# hex-inverter.net
KiCad netlist of a schematic drawn in Altium Designer
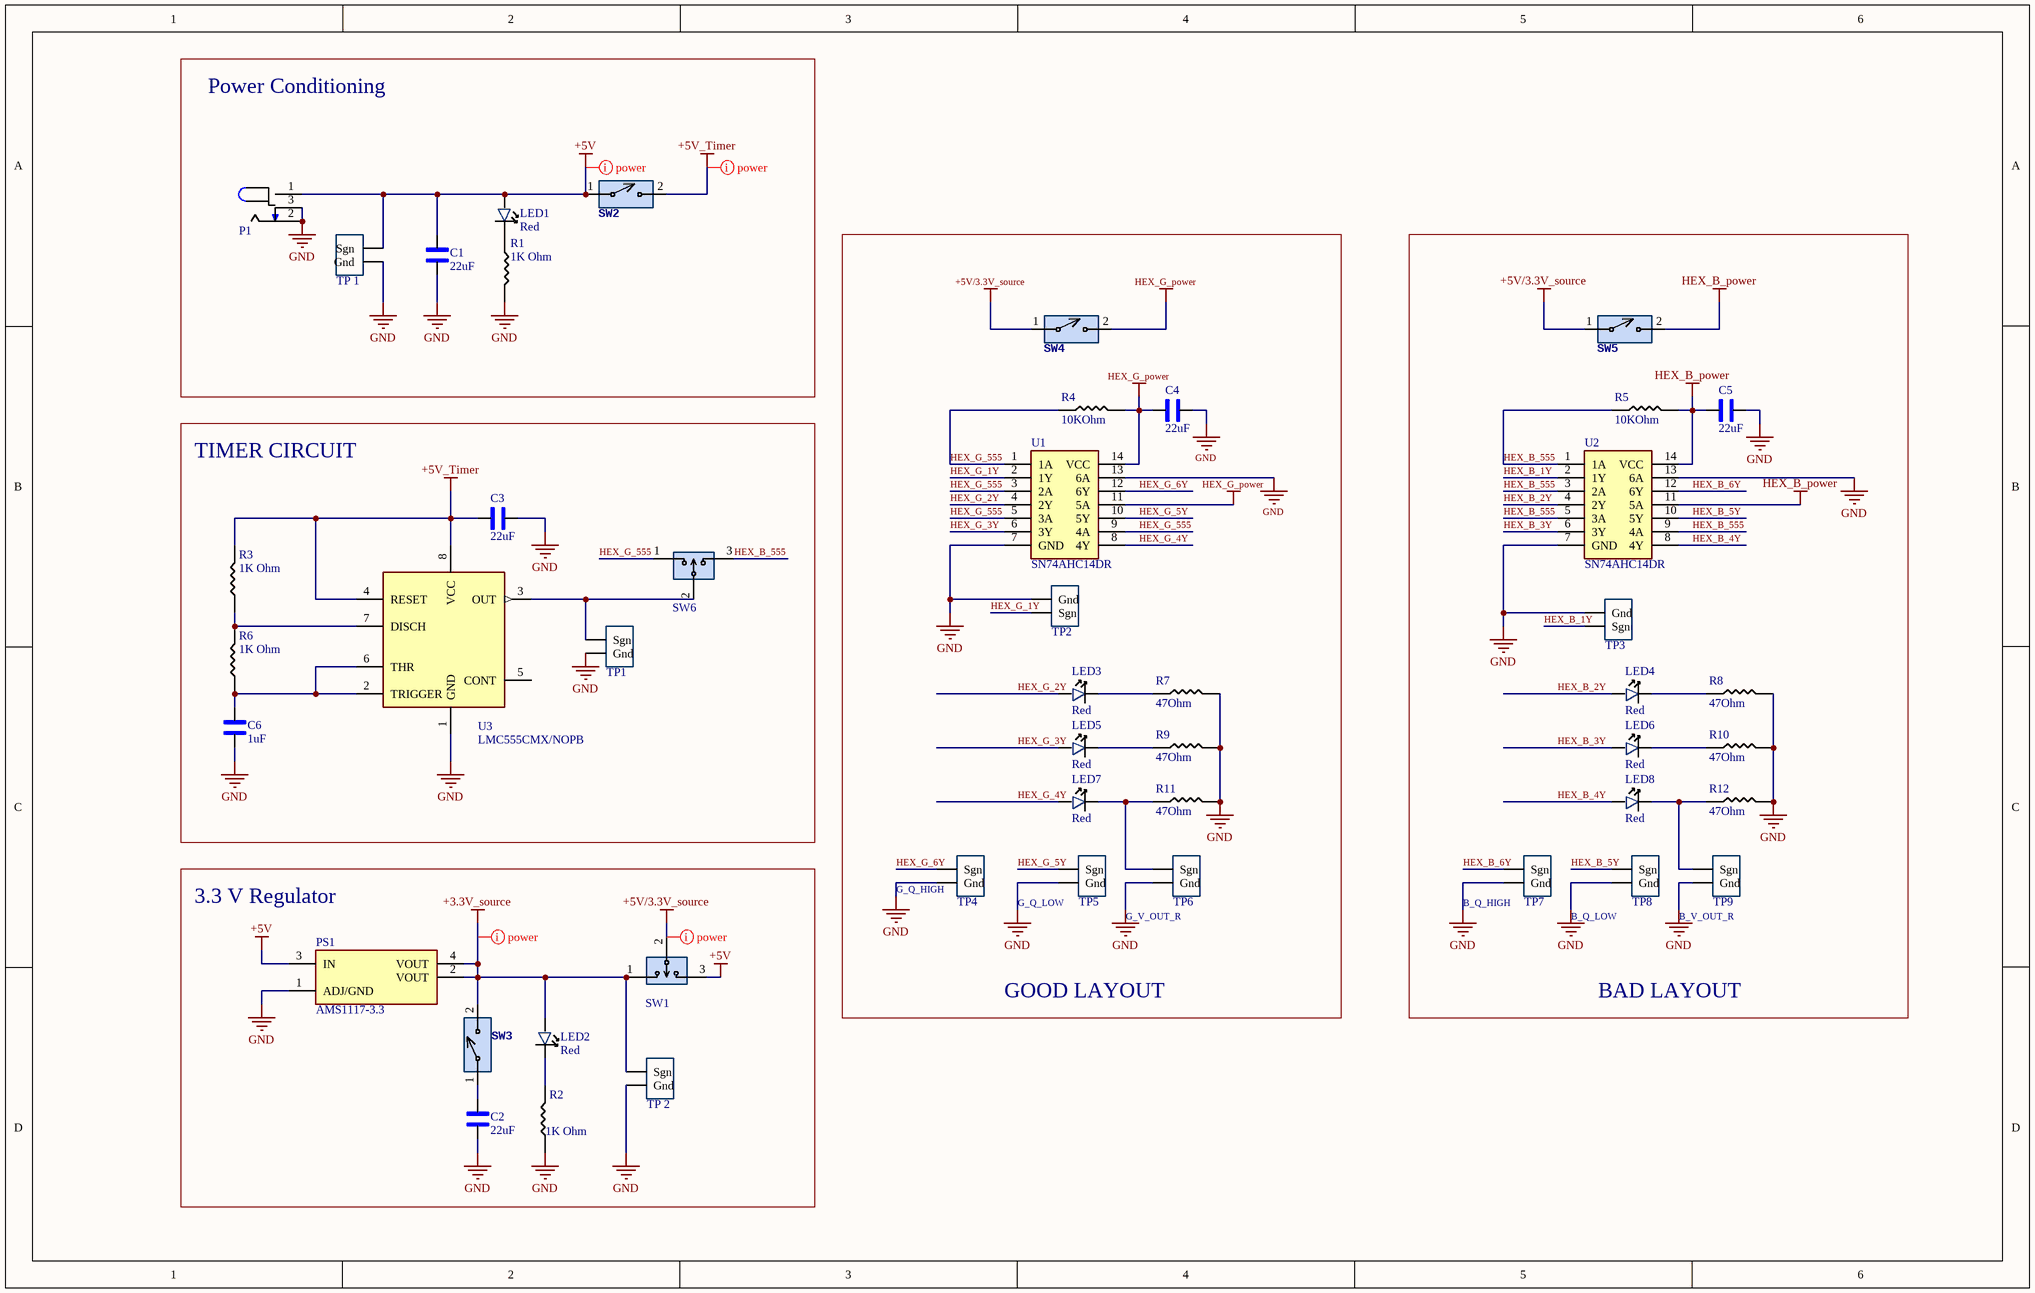
[diagram p0: hex-inverter.SchDoc]

(export (version "E")
  (design (tool "Eeschema 10.0.6"))
  (components
    (comp (ref "C1")
      (value "22uF")
      (footprint "1206_Passive_Capacitor")
      (description "22uF ±10% 25V X5R 1206 Multilayer Ceramic Capacitors MLCC - SMD/SMT RoHS")
      (fields (field (name "MFR PART #") "CL31A226KAHNNNE") (field (name "LCSC PART#") "C12891"))
      (libsource (lib "ECEN5730Lib_2023_05_DS") (part "C_22uF_1206"))
    )
    (comp (ref "C2")
      (value "22uF")
      (footprint "1206_Passive_Capacitor")
      (description "22uF ±10% 25V X5R 1206 Multilayer Ceramic Capacitors MLCC - SMD/SMT RoHS")
      (fields (field (name "MFR PART #") "CL31A226KAHNNNE") (field (name "LCSC PART#") "C12891"))
      (libsource (lib "ECEN5730Lib_2023_05_DS") (part "C_22uF_1206"))
    )
    (comp (ref "C3")
      (value "22uF")
      (footprint "1206_Passive_Capacitor")
      (description "22uF ±10% 25V X5R 1206 Multilayer Ceramic Capacitors MLCC - SMD/SMT RoHS")
      (fields (field (name "MFR PART #") "CL31A226KAHNNNE") (field (name "LCSC PART#") "C12891"))
      (libsource (lib "ECEN5730Lib_2023_05_DS") (part "C_22uF_1206"))
    )
    (comp (ref "C4")
      (value "22uF")
      (footprint "1206_Passive_Capacitor")
      (description "22uF ±10% 25V X5R 1206 Multilayer Ceramic Capacitors MLCC - SMD/SMT RoHS")
      (fields (field (name "MFR PART #") "CL31A226KAHNNNE") (field (name "LCSC PART#") "C12891"))
      (libsource (lib "ECEN5730Lib_2023_05_DS") (part "C_22uF_1206"))
    )
    (comp (ref "C5")
      (value "22uF")
      (footprint "1206_Passive_Capacitor")
      (description "22uF ±10% 25V X5R 1206 Multilayer Ceramic Capacitors MLCC - SMD/SMT RoHS")
      (fields (field (name "MFR PART #") "CL31A226KAHNNNE") (field (name "LCSC PART#") "C12891"))
      (libsource (lib "ECEN5730Lib_2023_05_DS") (part "C_22uF_1206"))
    )
    (comp (ref "C6")
      (value "1uF")
      (footprint "1206_Passive_Capacitor")
      (description "MULTILAYER CERAMIC CAPACITORS MLCC - SMD/SMT 1UF 50V 1206 ROHS")
      (fields (field (name "MFR PART #") "CL31B105KBHNNNE") (field (name "LCSC PART#") "C1848"))
      (libsource (lib "ECEN5730Lib_2023_05_DS") (part "C_1uF_1206"))
    )
    (comp (ref "LED1")
      (value "Red")
      (footprint "LED_1206")
      (description "Red 621~631nm 1206 Light Emitting Diodes (LED) RoHS")
      (fields (field (name "MFR PART #") "15-21/R6C-FQ1R1B/2T") (field (name "LCSC PART#") "C93133"))
      (libsource (lib "ECEN5730Lib_2023_05_DS") (part "LED_RED_1206"))
    )
    (comp (ref "LED2")
      (value "Red")
      (footprint "LED_1206")
      (description "Red 621~631nm 1206 Light Emitting Diodes (LED) RoHS")
      (fields (field (name "MFR PART #") "15-21/R6C-FQ1R1B/2T") (field (name "LCSC PART#") "C93133"))
      (libsource (lib "ECEN5730Lib_2023_05_DS") (part "LED_RED_1206"))
    )
    (comp (ref "LED3")
      (value "Red")
      (footprint "LED_1206")
      (description "Red 621~631nm 1206 Light Emitting Diodes (LED) RoHS")
      (fields (field (name "MFR PART #") "15-21/R6C-FQ1R1B/2T") (field (name "LCSC PART#") "C93133"))
      (libsource (lib "ECEN5730Lib_2023_05_DS") (part "LED_RED_1206"))
    )
    (comp (ref "LED4")
      (value "Red")
      (footprint "LED_1206")
      (description "Red 621~631nm 1206 Light Emitting Diodes (LED) RoHS")
      (fields (field (name "MFR PART #") "15-21/R6C-FQ1R1B/2T") (field (name "LCSC PART#") "C93133"))
      (libsource (lib "ECEN5730Lib_2023_05_DS") (part "LED_RED_1206"))
    )
    (comp (ref "LED5")
      (value "Red")
      (footprint "LED_1206")
      (description "Red 621~631nm 1206 Light Emitting Diodes (LED) RoHS")
      (fields (field (name "MFR PART #") "15-21/R6C-FQ1R1B/2T") (field (name "LCSC PART#") "C93133"))
      (libsource (lib "ECEN5730Lib_2023_05_DS") (part "LED_RED_1206"))
    )
    (comp (ref "LED6")
      (value "Red")
      (footprint "LED_1206")
      (description "Red 621~631nm 1206 Light Emitting Diodes (LED) RoHS")
      (fields (field (name "MFR PART #") "15-21/R6C-FQ1R1B/2T") (field (name "LCSC PART#") "C93133"))
      (libsource (lib "ECEN5730Lib_2023_05_DS") (part "LED_RED_1206"))
    )
    (comp (ref "LED7")
      (value "Red")
      (footprint "LED_1206")
      (description "Red 621~631nm 1206 Light Emitting Diodes (LED) RoHS")
      (fields (field (name "MFR PART #") "15-21/R6C-FQ1R1B/2T") (field (name "LCSC PART#") "C93133"))
      (libsource (lib "ECEN5730Lib_2023_05_DS") (part "LED_RED_1206"))
    )
    (comp (ref "LED8")
      (value "Red")
      (footprint "LED_1206")
      (description "Red 621~631nm 1206 Light Emitting Diodes (LED) RoHS")
      (fields (field (name "MFR PART #") "15-21/R6C-FQ1R1B/2T") (field (name "LCSC PART#") "C93133"))
      (libsource (lib "ECEN5730Lib_2023_05_DS") (part "LED_RED_1206"))
    )
    (comp (ref "P1")
      (value "Power Jack")
      (footprint "Power_Jack")
      (description "Power Barrel Connector Jack 2.10mm ID (0.083\"), 5.50mm OD (0.217\") Through Hole, Right Angle")
      (fields (field (name "MFR PART #") "PJ-102A") (field (name "LCSC PART#") "C136744"))
      (libsource (lib "ECEN5730Lib_2023_05_DS") (part "P_Power Jack"))
    )
    (comp (ref "PS1")
      (value "AMS1117-3.3")
      (footprint "LDO")
      (description "LOW DROPOUT REGULATORS(LDO) POSITIVE FIXED 1.3V @ 800MA 15V 3.3V 1A SOT-223 ROHS")
      (fields (field (name "LCSC PART#") "C6186"))
      (libsource (lib "ECEN5730Lib_2023_05_DS") (part "PS_AMS_LDO_3v3"))
    )
    (comp (ref "R1")
      (value "1K Ohm")
      (footprint "1206_Passive_Resitor")
      (description "CHIP RESISTOR - SURFACE MOUNT 1KOHMS ±1% 1/4W 1206 ROHS")
      (fields (field (name "MFR PART #") "RNCP1206FTD1K00CT") (field (name "LCSC PART#") "C4410"))
      (libsource (lib "ECEN5730Lib_2023_05_DS") (part "R_1K_1206"))
    )
    (comp (ref "R2")
      (value "1K Ohm")
      (footprint "1206_Passive_Resitor")
      (description "CHIP RESISTOR - SURFACE MOUNT 1KOHMS ±1% 1/4W 1206 ROHS")
      (fields (field (name "MFR PART #") "RNCP1206FTD1K00CT") (field (name "LCSC PART#") "C4410"))
      (libsource (lib "ECEN5730Lib_2023_05_DS") (part "R_1K_1206"))
    )
    (comp (ref "R3")
      (value "1K Ohm")
      (footprint "1206_Passive_Resitor")
      (description "CHIP RESISTOR - SURFACE MOUNT 1KOHMS ±1% 1/4W 1206 ROHS")
      (fields (field (name "MFR PART #") "RNCP1206FTD1K00CT") (field (name "LCSC PART#") "C4410"))
      (libsource (lib "ECEN5730Lib_2023_05_DS") (part "R_1K_1206"))
    )
    (comp (ref "R4")
      (value "10KOhm")
      (footprint "1206_Passive_Resitor")
      (description "10 kOhms ±5% 0.25W, 1/4W Chip Resistor 1206 (3216 Metric) Automotive AEC-Q200 Thick Film")
      (fields (field (name "MFR PART #") "RMCF1206FT10K0") (field (name "LCSC PART#") "C17902"))
      (libsource (lib "ECEN5730Lib_2023_05_DS") (part "R_10KOhm_1206"))
    )
    (comp (ref "R5")
      (value "10KOhm")
      (footprint "1206_Passive_Resitor")
      (description "10 kOhms ±5% 0.25W, 1/4W Chip Resistor 1206 (3216 Metric) Automotive AEC-Q200 Thick Film")
      (fields (field (name "MFR PART #") "RMCF1206FT10K0") (field (name "LCSC PART#") "C17902"))
      (libsource (lib "ECEN5730Lib_2023_05_DS") (part "R_10KOhm_1206"))
    )
    (comp (ref "R6")
      (value "1K Ohm")
      (footprint "1206_Passive_Resitor")
      (description "CHIP RESISTOR - SURFACE MOUNT 1KOHMS ±1% 1/4W 1206 ROHS")
      (fields (field (name "MFR PART #") "RNCP1206FTD1K00CT") (field (name "LCSC PART#") "C4410"))
      (libsource (lib "ECEN5730Lib_2023_05_DS") (part "R_1K_1206"))
    )
    (comp (ref "R7")
      (value "47Ohm")
      (footprint "1206_Passive_Resitor")
      (description "47Ω ±5% 0.25W ±200ppm/℃ 1206 Chip Resistor - Surface Mount RoHS")
      (fields (field (name "MFR PART #") "1206W4J0470T5E") (field (name "LCSC PART#") "C25384"))
      (libsource (lib "ECEN5730Lib_2023_05_DS") (part "R_47Ohm_1206"))
    )
    (comp (ref "R8")
      (value "47Ohm")
      (footprint "1206_Passive_Resitor")
      (description "47Ω ±5% 0.25W ±200ppm/℃ 1206 Chip Resistor - Surface Mount RoHS")
      (fields (field (name "MFR PART #") "1206W4J0470T5E") (field (name "LCSC PART#") "C25384"))
      (libsource (lib "ECEN5730Lib_2023_05_DS") (part "R_47Ohm_1206"))
    )
    (comp (ref "R9")
      (value "47Ohm")
      (footprint "1206_Passive_Resitor")
      (description "47Ω ±5% 0.25W ±200ppm/℃ 1206 Chip Resistor - Surface Mount RoHS")
      (fields (field (name "MFR PART #") "1206W4J0470T5E") (field (name "LCSC PART#") "C25384"))
      (libsource (lib "ECEN5730Lib_2023_05_DS") (part "R_47Ohm_1206"))
    )
    (comp (ref "R10")
      (value "47Ohm")
      (footprint "1206_Passive_Resitor")
      (description "47Ω ±5% 0.25W ±200ppm/℃ 1206 Chip Resistor - Surface Mount RoHS")
      (fields (field (name "MFR PART #") "1206W4J0470T5E") (field (name "LCSC PART#") "C25384"))
      (libsource (lib "ECEN5730Lib_2023_05_DS") (part "R_47Ohm_1206"))
    )
    (comp (ref "R11")
      (value "47Ohm")
      (footprint "1206_Passive_Resitor")
      (description "47Ω ±5% 0.25W ±200ppm/℃ 1206 Chip Resistor - Surface Mount RoHS")
      (fields (field (name "MFR PART #") "1206W4J0470T5E") (field (name "LCSC PART#") "C25384"))
      (libsource (lib "ECEN5730Lib_2023_05_DS") (part "R_47Ohm_1206"))
    )
    (comp (ref "R12")
      (value "47Ohm")
      (footprint "1206_Passive_Resitor")
      (description "47Ω ±5% 0.25W ±200ppm/℃ 1206 Chip Resistor - Surface Mount RoHS")
      (fields (field (name "MFR PART #") "1206W4J0470T5E") (field (name "LCSC PART#") "C25384"))
      (libsource (lib "ECEN5730Lib_2023_05_DS") (part "R_47Ohm_1206"))
    )
    (comp (ref "SW1")
      (value "PREC003SAAN-RC")
      (footprint "3_PIN_100mil")
      (description "Connector Header Through Hole 3 position 0.100\" (2.54mm)")
      (fields (field (name "LCSC PART#") "C49257"))
      (libsource (lib "ECEN5730Lib_2023_05_DS") (part "SW_3Pin_100mil_Switch"))
    )
    (comp (ref "SW2")
      (value "SW_2Pin_100mil_Switch")
      (footprint "2Pin-Header-Conn")
      (description "2Pin Header")
      (fields (field (name "LCSC PART#") "C124375"))
      (libsource (lib "ECEN5730Lib_2023_05_DS") (part "SW_2Pin_100mil_Switch"))
    )
    (comp (ref "SW3")
      (value "SW_2Pin_100mil_Switch")
      (footprint "2Pin-Header-Conn")
      (description "2Pin Header")
      (fields (field (name "LCSC PART#") "C124375"))
      (libsource (lib "") (part "SW_2Pin_100mil_Switch_1"))
    )
    (comp (ref "SW4")
      (value "SW_2Pin_100mil_Switch")
      (footprint "2Pin-Header-Conn")
      (description "2Pin Header")
      (fields (field (name "LCSC PART#") "C124375"))
      (libsource (lib "ECEN5730Lib_2023_05_DS") (part "SW_2Pin_100mil_Switch"))
    )
    (comp (ref "SW5")
      (value "SW_2Pin_100mil_Switch")
      (footprint "2Pin-Header-Conn")
      (description "2Pin Header")
      (fields (field (name "LCSC PART#") "C124375"))
      (libsource (lib "ECEN5730Lib_2023_05_DS") (part "SW_2Pin_100mil_Switch"))
    )
    (comp (ref "SW6")
      (value "PREC003SAAN-RC")
      (footprint "3_PIN_100mil")
      (description "Connector Header Through Hole 3 position 0.100\" (2.54mm)")
      (fields (field (name "LCSC PART#") "C49257"))
      (libsource (lib "") (part "SW_3Pin_100mil_Switch_1"))
    )
    (comp (ref "TP 1")
      (value "10x Probe TP")
      (footprint "TP10x_Probe")
      (description "Test Point 300 mil centers")
      (libsource (lib "") (part "TP_10x_Probe_2"))
    )
    (comp (ref "TP 2")
      (value "10x Probe TP")
      (footprint "TP10x_Probe")
      (description "Test Point 300 mil centers")
      (libsource (lib "ECEN5730Lib_2023_05_DS") (part "TP_10x_Probe"))
    )
    (comp (ref "TP1")
      (value "10x Probe TP")
      (footprint "TP10x_Probe")
      (description "Test Point 300 mil centers")
      (libsource (lib "ECEN5730Lib_2023_05_DS") (part "TP_10x_Probe"))
    )
    (comp (ref "TP2")
      (value "10x Probe TP")
      (footprint "TP10x_Probe")
      (description "Test Point 300 mil centers")
      (libsource (lib "") (part "TP_10x_Probe_1"))
    )
    (comp (ref "TP3")
      (value "10x Probe TP")
      (footprint "TP10x_Probe")
      (description "Test Point 300 mil centers")
      (libsource (lib "") (part "TP_10x_Probe_1"))
    )
    (comp (ref "TP4")
      (value "10x Probe TP")
      (footprint "TP10x_Probe")
      (description "Test Point 300 mil centers")
      (libsource (lib "ECEN5730Lib_2023_05_DS") (part "TP_10x_Probe"))
    )
    (comp (ref "TP5")
      (value "10x Probe TP")
      (footprint "TP10x_Probe")
      (description "Test Point 300 mil centers")
      (libsource (lib "ECEN5730Lib_2023_05_DS") (part "TP_10x_Probe"))
    )
    (comp (ref "TP6")
      (value "10x Probe TP")
      (footprint "TP10x_Probe")
      (description "Test Point 300 mil centers")
      (libsource (lib "ECEN5730Lib_2023_05_DS") (part "TP_10x_Probe"))
    )
    (comp (ref "TP7")
      (value "10x Probe TP")
      (footprint "TP10x_Probe")
      (description "Test Point 300 mil centers")
      (libsource (lib "ECEN5730Lib_2023_05_DS") (part "TP_10x_Probe"))
    )
    (comp (ref "TP8")
      (value "10x Probe TP")
      (footprint "TP10x_Probe")
      (description "Test Point 300 mil centers")
      (libsource (lib "ECEN5730Lib_2023_05_DS") (part "TP_10x_Probe"))
    )
    (comp (ref "TP9")
      (value "10x Probe TP")
      (footprint "TP10x_Probe")
      (description "Test Point 300 mil centers")
      (libsource (lib "ECEN5730Lib_2023_05_DS") (part "TP_10x_Probe"))
    )
    (comp (ref "U1")
      (value "SN74AHC14DR")
      (footprint "HEX_74AC14")
      (description "Inverter IC 6 Channel Schmitt Trigger 14-SOIC")
      (fields (field (name "LCSC PART#") "C6942"))
      (libsource (lib "ECEN5730Lib_2023_05_DS") (part "U_74AHC14"))
    )
    (comp (ref "U2")
      (value "SN74AHC14DR")
      (footprint "HEX_74AC14")
      (description "Inverter IC 6 Channel Schmitt Trigger 14-SOIC")
      (fields (field (name "LCSC PART#") "C6942"))
      (libsource (lib "ECEN5730Lib_2023_05_DS") (part "U_74AHC14"))
    )
    (comp (ref "U3")
      (value "LMC555CMX/NOPB")
      (footprint "TS555IDTTR")
      (description "555 Type, Timer/Oscillator _Single_ IC 3MHz 8-SO")
      (fields (field (name "LCSC PART#") "C90760"))
      (libsource (lib "ECEN5730Lib_2023_05_DS") (part "U_555_Fast"))
    )
  )
  (nets
    (net (code "1") (name "+3.3V_source") (class "Default")
      (node (ref "LED2") (pin "1") (pinfunction "1_1") (pintype "passive"))
      (node (ref "PS1") (pin "2") (pinfunction "VOUT_2") (pintype "power_in"))
      (node (ref "PS1") (pin "4") (pinfunction "VOUT_4") (pintype "power_in"))
      (node (ref "SW1") (pin "1") (pinfunction "1_1") (pintype "passive"))
      (node (ref "SW3") (pin "2") (pinfunction "2_2") (pintype "passive"))
      (node (ref "TP 2") (pin "1") (pinfunction "Sgn_1") (pintype "passive"))
    )
    (net (code "2") (name "+5V") (class "Default")
      (node (ref "C1") (pin "2") (pinfunction "2_2") (pintype "passive"))
      (node (ref "LED1") (pin "1") (pinfunction "1_1") (pintype "passive"))
      (node (ref "P1") (pin "1") (pinfunction "1_1") (pintype "power_in"))
      (node (ref "PS1") (pin "3") (pinfunction "IN_3") (pintype "power_in"))
      (node (ref "SW1") (pin "3") (pinfunction "3_3") (pintype "passive"))
      (node (ref "SW2") (pin "1") (pinfunction "1_1") (pintype "passive"))
      (node (ref "TP 1") (pin "1") (pinfunction "Sgn_1") (pintype "passive"))
    )
    (net (code "3") (name "+5V_Timer") (class "Default")
      (node (ref "C3") (pin "2") (pinfunction "2_2") (pintype "passive"))
      (node (ref "R3") (pin "2") (pinfunction "2_2") (pintype "passive"))
      (node (ref "SW2") (pin "2") (pinfunction "2_2") (pintype "passive"))
      (node (ref "U3") (pin "4") (pinfunction "RESET_4") (pintype "passive"))
      (node (ref "U3") (pin "8") (pinfunction "VCC_8") (pintype "power_in"))
    )
    (net (code "4") (name "+5V{slash}3.3V_source") (class "Default")
      (node (ref "SW1") (pin "2") (pinfunction "2_2") (pintype "passive"))
      (node (ref "SW4") (pin "1") (pinfunction "1_1") (pintype "passive"))
      (node (ref "SW5") (pin "1") (pinfunction "1_1") (pintype "passive"))
    )
    (net (code "5") (name "/HEX_B_1Y") (class "Default")
      (node (ref "TP3") (pin "1") (pinfunction "Sgn_1") (pintype "passive"))
      (node (ref "U2") (pin "2") (pinfunction "1Y_2") (pintype "passive"))
    )
    (net (code "6") (name "/HEX_B_2Y") (class "Default")
      (node (ref "LED4") (pin "1") (pinfunction "1_1") (pintype "passive"))
      (node (ref "U2") (pin "4") (pinfunction "2Y_4") (pintype "passive"))
    )
    (net (code "7") (name "/HEX_B_3Y") (class "Default")
      (node (ref "LED6") (pin "1") (pinfunction "1_1") (pintype "passive"))
      (node (ref "U2") (pin "6") (pinfunction "3Y_6") (pintype "passive"))
    )
    (net (code "8") (name "/HEX_B_4Y") (class "Default")
      (node (ref "LED8") (pin "1") (pinfunction "1_1") (pintype "passive"))
      (node (ref "U2") (pin "8") (pinfunction "4Y_8") (pintype "passive"))
    )
    (net (code "9") (name "/HEX_B_5Y") (class "Default")
      (node (ref "TP8") (pin "1") (pinfunction "Sgn_1") (pintype "passive"))
      (node (ref "U2") (pin "10") (pinfunction "5Y_10") (pintype "passive"))
    )
    (net (code "10") (name "/HEX_B_6Y") (class "Default")
      (node (ref "TP7") (pin "1") (pinfunction "Sgn_1") (pintype "passive"))
      (node (ref "U2") (pin "12") (pinfunction "6Y_12") (pintype "passive"))
    )
    (net (code "11") (name "/HEX_B_555") (class "Default")
      (node (ref "R5") (pin "1") (pinfunction "1_1") (pintype "passive"))
      (node (ref "SW6") (pin "3") (pinfunction "3_3") (pintype "passive"))
      (node (ref "U2") (pin "1") (pinfunction "1A_1") (pintype "passive"))
      (node (ref "U2") (pin "3") (pinfunction "2A_3") (pintype "passive"))
      (node (ref "U2") (pin "5") (pinfunction "3A_5") (pintype "passive"))
      (node (ref "U2") (pin "9") (pinfunction "4A_9") (pintype "passive"))
    )
    (net (code "12") (name "/HEX_G_1Y") (class "Default")
      (node (ref "TP2") (pin "1") (pinfunction "Sgn_1") (pintype "passive"))
      (node (ref "U1") (pin "2") (pinfunction "1Y_2") (pintype "passive"))
    )
    (net (code "13") (name "/HEX_G_2Y") (class "Default")
      (node (ref "LED3") (pin "1") (pinfunction "1_1") (pintype "passive"))
      (node (ref "U1") (pin "4") (pinfunction "2Y_4") (pintype "passive"))
    )
    (net (code "14") (name "/HEX_G_3Y") (class "Default")
      (node (ref "LED5") (pin "1") (pinfunction "1_1") (pintype "passive"))
      (node (ref "U1") (pin "6") (pinfunction "3Y_6") (pintype "passive"))
    )
    (net (code "15") (name "/HEX_G_4Y") (class "Default")
      (node (ref "LED7") (pin "1") (pinfunction "1_1") (pintype "passive"))
      (node (ref "U1") (pin "8") (pinfunction "4Y_8") (pintype "passive"))
    )
    (net (code "16") (name "/HEX_G_5Y") (class "Default")
      (node (ref "TP5") (pin "1") (pinfunction "Sgn_1") (pintype "passive"))
      (node (ref "U1") (pin "10") (pinfunction "5Y_10") (pintype "passive"))
    )
    (net (code "17") (name "/HEX_G_6Y") (class "Default")
      (node (ref "TP4") (pin "1") (pinfunction "Sgn_1") (pintype "passive"))
      (node (ref "U1") (pin "12") (pinfunction "6Y_12") (pintype "passive"))
    )
    (net (code "18") (name "/HEX_G_555") (class "Default")
      (node (ref "R4") (pin "1") (pinfunction "1_1") (pintype "passive"))
      (node (ref "SW6") (pin "1") (pinfunction "1_1") (pintype "passive"))
      (node (ref "U1") (pin "1") (pinfunction "1A_1") (pintype "passive"))
      (node (ref "U1") (pin "3") (pinfunction "2A_3") (pintype "passive"))
      (node (ref "U1") (pin "5") (pinfunction "3A_5") (pintype "passive"))
      (node (ref "U1") (pin "9") (pinfunction "4A_9") (pintype "passive"))
    )
    (net (code "19") (name "GND") (class "Default")
      (node (ref "C1") (pin "1") (pinfunction "1_1") (pintype "passive"))
      (node (ref "C2") (pin "1") (pinfunction "1_1") (pintype "passive"))
      (node (ref "C3") (pin "1") (pinfunction "1_1") (pintype "passive"))
      (node (ref "C4") (pin "1") (pinfunction "1_1") (pintype "passive"))
      (node (ref "C5") (pin "1") (pinfunction "1_1") (pintype "passive"))
      (node (ref "C6") (pin "1") (pinfunction "1_1") (pintype "passive"))
      (node (ref "P1") (pin "2") (pinfunction "2_2") (pintype "power_in"))
      (node (ref "P1") (pin "3") (pinfunction "3_3") (pintype "power_in"))
      (node (ref "PS1") (pin "1") (pinfunction "ADJ/GND_1") (pintype "passive"))
      (node (ref "R1") (pin "2") (pinfunction "2_2") (pintype "passive"))
      (node (ref "R10") (pin "2") (pinfunction "2_2") (pintype "passive"))
      (node (ref "R11") (pin "2") (pinfunction "2_2") (pintype "passive"))
      (node (ref "R12") (pin "2") (pinfunction "2_2") (pintype "passive"))
      (node (ref "R2") (pin "1") (pinfunction "1_1") (pintype "passive"))
      (node (ref "R7") (pin "2") (pinfunction "2_2") (pintype "passive"))
      (node (ref "R8") (pin "2") (pinfunction "2_2") (pintype "passive"))
      (node (ref "R9") (pin "2") (pinfunction "2_2") (pintype "passive"))
      (node (ref "TP 1") (pin "2") (pinfunction "Gnd_2") (pintype "passive"))
      (node (ref "TP 2") (pin "2") (pinfunction "Gnd_2") (pintype "passive"))
      (node (ref "TP1") (pin "2") (pinfunction "Gnd_2") (pintype "passive"))
      (node (ref "TP2") (pin "2") (pinfunction "Gnd_2") (pintype "passive"))
      (node (ref "TP3") (pin "2") (pinfunction "Gnd_2") (pintype "passive"))
      (node (ref "TP4") (pin "2") (pinfunction "Gnd_2") (pintype "passive"))
      (node (ref "TP5") (pin "2") (pinfunction "Gnd_2") (pintype "passive"))
      (node (ref "TP6") (pin "2") (pinfunction "Gnd_2") (pintype "passive"))
      (node (ref "TP7") (pin "2") (pinfunction "Gnd_2") (pintype "passive"))
      (node (ref "TP8") (pin "2") (pinfunction "Gnd_2") (pintype "passive"))
      (node (ref "TP9") (pin "2") (pinfunction "Gnd_2") (pintype "passive"))
      (node (ref "U1") (pin "13") (pinfunction "6A_13") (pintype "passive"))
      (node (ref "U1") (pin "7") (pinfunction "GND_7") (pintype "passive"))
      (node (ref "U2") (pin "13") (pinfunction "6A_13") (pintype "passive"))
      (node (ref "U2") (pin "7") (pinfunction "GND_7") (pintype "passive"))
      (node (ref "U3") (pin "1") (pinfunction "GND_1") (pintype "power_in"))
    )
    (net (code "20") (name "HEX_B_power") (class "Default")
      (node (ref "C5") (pin "2") (pinfunction "2_2") (pintype "passive"))
      (node (ref "R5") (pin "2") (pinfunction "2_2") (pintype "passive"))
      (node (ref "SW5") (pin "2") (pinfunction "2_2") (pintype "passive"))
      (node (ref "U2") (pin "11") (pinfunction "5A_11") (pintype "passive"))
      (node (ref "U2") (pin "14") (pinfunction "VCC_14") (pintype "passive"))
    )
    (net (code "21") (name "HEX_G_power") (class "Default")
      (node (ref "C4") (pin "2") (pinfunction "2_2") (pintype "passive"))
      (node (ref "R4") (pin "2") (pinfunction "2_2") (pintype "passive"))
      (node (ref "SW4") (pin "2") (pinfunction "2_2") (pintype "passive"))
      (node (ref "U1") (pin "11") (pinfunction "5A_11") (pintype "passive"))
      (node (ref "U1") (pin "14") (pinfunction "VCC_14") (pintype "passive"))
    )
    (net (code "22") (name "Net-(C2-Pad2)") (class "Default")
      (node (ref "C2") (pin "2") (pinfunction "2_2") (pintype "passive"))
      (node (ref "SW3") (pin "1") (pinfunction "1_1") (pintype "passive"))
    )
    (net (code "23") (name "Net-(LED1-Pad2)") (class "Default")
      (node (ref "LED1") (pin "2") (pinfunction "2_2") (pintype "passive"))
      (node (ref "R1") (pin "1") (pinfunction "1_1") (pintype "passive"))
    )
    (net (code "24") (name "Net-(LED2-Pad2)") (class "Default")
      (node (ref "LED2") (pin "2") (pinfunction "2_2") (pintype "passive"))
      (node (ref "R2") (pin "2") (pinfunction "2_2") (pintype "passive"))
    )
    (net (code "25") (name "Net-(LED3-Pad2)") (class "Default")
      (node (ref "LED3") (pin "2") (pinfunction "2_2") (pintype "passive"))
      (node (ref "R7") (pin "1") (pinfunction "1_1") (pintype "passive"))
    )
    (net (code "26") (name "Net-(LED4-Pad2)") (class "Default")
      (node (ref "LED4") (pin "2") (pinfunction "2_2") (pintype "passive"))
      (node (ref "R8") (pin "1") (pinfunction "1_1") (pintype "passive"))
    )
    (net (code "27") (name "Net-(LED5-Pad2)") (class "Default")
      (node (ref "LED5") (pin "2") (pinfunction "2_2") (pintype "passive"))
      (node (ref "R9") (pin "1") (pinfunction "1_1") (pintype "passive"))
    )
    (net (code "28") (name "Net-(LED6-Pad2)") (class "Default")
      (node (ref "LED6") (pin "2") (pinfunction "2_2") (pintype "passive"))
      (node (ref "R10") (pin "1") (pinfunction "1_1") (pintype "passive"))
    )
    (net (code "29") (name "Net-(TP1-Sgn)") (class "Default")
      (node (ref "SW6") (pin "2") (pinfunction "2_2") (pintype "passive"))
      (node (ref "TP1") (pin "1") (pinfunction "Sgn_1") (pintype "passive"))
      (node (ref "U3") (pin "3") (pinfunction "OUT_3") (pintype "output"))
    )
    (net (code "30") (name "Net-(TP6-Sgn)") (class "Default")
      (node (ref "LED7") (pin "2") (pinfunction "2_2") (pintype "passive"))
      (node (ref "R11") (pin "1") (pinfunction "1_1") (pintype "passive"))
      (node (ref "TP6") (pin "1") (pinfunction "Sgn_1") (pintype "passive"))
    )
    (net (code "31") (name "Net-(TP9-Sgn)") (class "Default")
      (node (ref "LED8") (pin "2") (pinfunction "2_2") (pintype "passive"))
      (node (ref "R12") (pin "1") (pinfunction "1_1") (pintype "passive"))
      (node (ref "TP9") (pin "1") (pinfunction "Sgn_1") (pintype "passive"))
    )
    (net (code "32") (name "Net-(U3-DISCH)") (class "Default")
      (node (ref "R3") (pin "1") (pinfunction "1_1") (pintype "passive"))
      (node (ref "R6") (pin "2") (pinfunction "2_2") (pintype "passive"))
      (node (ref "U3") (pin "7") (pinfunction "DISCH_7") (pintype "passive"))
    )
    (net (code "33") (name "Net-(U3-THR)") (class "Default")
      (node (ref "C6") (pin "2") (pinfunction "2_2") (pintype "passive"))
      (node (ref "R6") (pin "1") (pinfunction "1_1") (pintype "passive"))
      (node (ref "U3") (pin "2") (pinfunction "TRIGGER_2") (pintype "passive"))
      (node (ref "U3") (pin "6") (pinfunction "THR_6") (pintype "passive"))
    )
    (net (code "34") (name "unconnected-(U3-CONT-Pad5)") (class "Default")
      (node (ref "U3") (pin "5") (pinfunction "CONT_5") (pintype "passive"))
    )
  )
)
